# MSboard.net
KiCad netlist of a schematic drawn in EAGLE
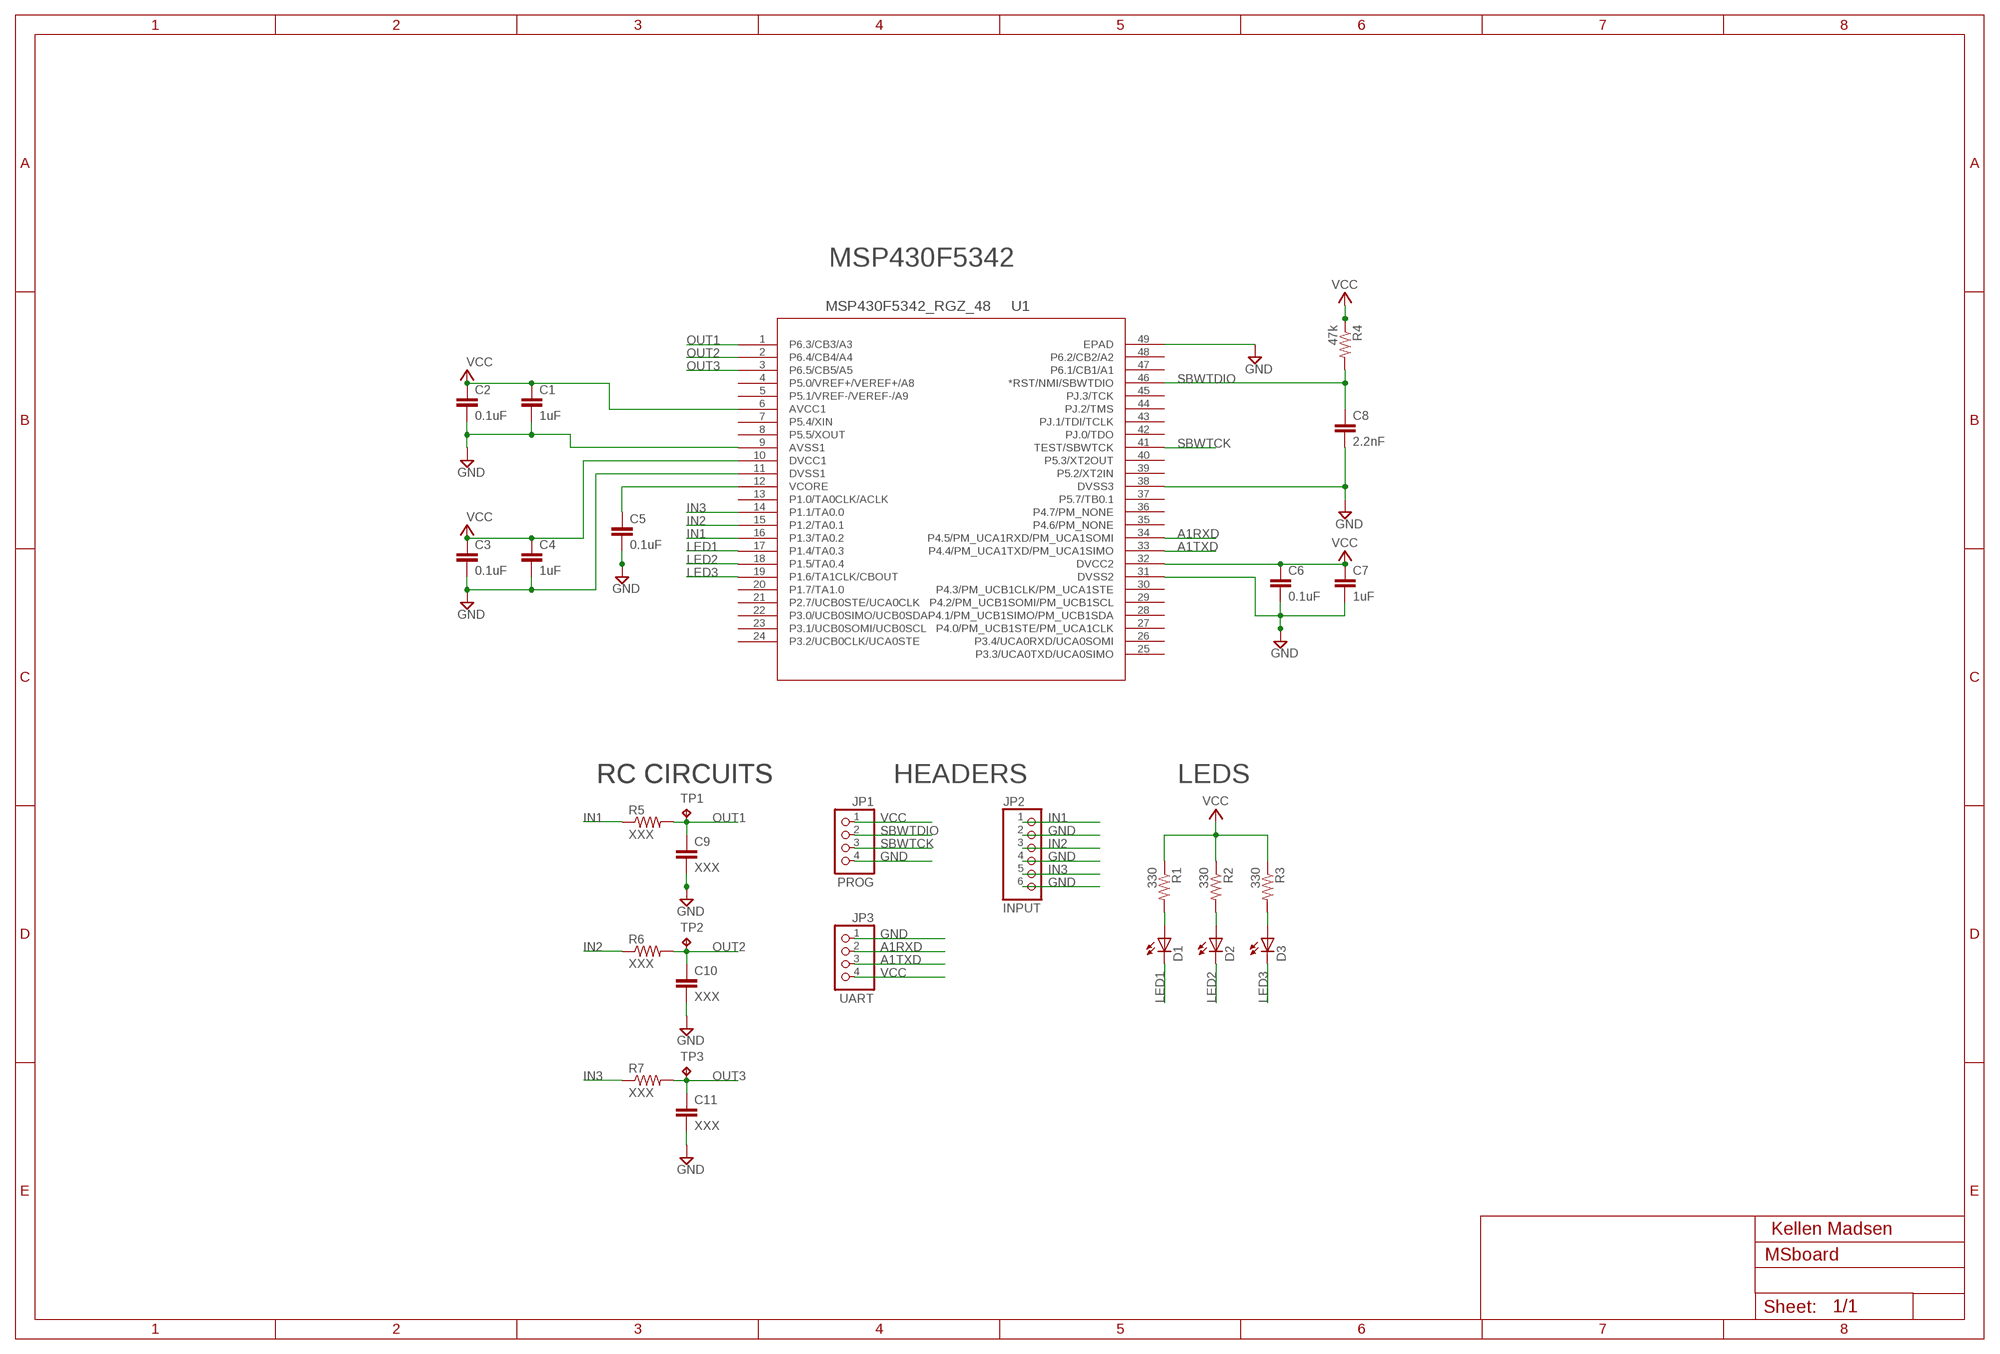
[diagram p0: schematic, sheet 1]

(export (version "E")
  (design (tool "Eeschema 10.0.6"))
  (components
    (comp (ref "C1")
      (value "1uF")
      (footprint "eagle-import:C0603")
      (libsource (lib "eagle-import") (part "C-EUC0603"))
    )
    (comp (ref "C2")
      (value "0.1uF")
      (footprint "eagle-import:C0603")
      (libsource (lib "eagle-import") (part "C-EUC0603"))
    )
    (comp (ref "C3")
      (value "0.1uF")
      (footprint "eagle-import:C0603")
      (libsource (lib "eagle-import") (part "C-EUC0603"))
    )
    (comp (ref "C4")
      (value "1uF")
      (footprint "eagle-import:C0603")
      (libsource (lib "eagle-import") (part "C-EUC0603"))
    )
    (comp (ref "C5")
      (value "0.1uF")
      (footprint "eagle-import:C0603")
      (libsource (lib "eagle-import") (part "C-EUC0603"))
    )
    (comp (ref "C6")
      (value "0.1uF")
      (footprint "eagle-import:C0603")
      (libsource (lib "eagle-import") (part "C-EUC0603"))
    )
    (comp (ref "C7")
      (value "1uF")
      (footprint "eagle-import:C0603")
      (libsource (lib "eagle-import") (part "C-EUC0603"))
    )
    (comp (ref "C8")
      (value "2.2nF")
      (footprint "eagle-import:C0603")
      (libsource (lib "eagle-import") (part "C-EUC0603"))
    )
    (comp (ref "C9")
      (value "XXX")
      (footprint "eagle-import:C0603")
      (libsource (lib "eagle-import") (part "C-EUC0603"))
    )
    (comp (ref "C10")
      (value "XXX")
      (footprint "eagle-import:C0603")
      (libsource (lib "eagle-import") (part "C-EUC0603"))
    )
    (comp (ref "C11")
      (value "XXX")
      (footprint "eagle-import:C0603")
      (libsource (lib "eagle-import") (part "C-EUC0603"))
    )
    (comp (ref "D1")
      (value "LEDCHIPLED_0603")
      (footprint "eagle-import:CHIPLED_0603")
      (libsource (lib "eagle-import") (part "LEDCHIPLED_0603"))
    )
    (comp (ref "D2")
      (value "LEDCHIPLED_0603")
      (footprint "eagle-import:CHIPLED_0603")
      (libsource (lib "eagle-import") (part "LEDCHIPLED_0603"))
    )
    (comp (ref "D3")
      (value "LEDCHIPLED_0603")
      (footprint "eagle-import:CHIPLED_0603")
      (libsource (lib "eagle-import") (part "LEDCHIPLED_0603"))
    )
    (comp (ref "JP1")
      (value "PROG")
      (footprint "eagle-import:1X04")
      (libsource (lib "eagle-import") (part "PINHD-1X4"))
    )
    (comp (ref "JP2")
      (value "INPUT")
      (footprint "eagle-import:1X06")
      (libsource (lib "eagle-import") (part "PINHD-1X6"))
    )
    (comp (ref "JP3")
      (value "UART")
      (footprint "eagle-import:1X04")
      (libsource (lib "eagle-import") (part "PINHD-1X4"))
    )
    (comp (ref "R1")
      (value "330")
      (footprint "eagle-import:R0603")
      (libsource (lib "eagle-import") (part "R-US_R0603"))
    )
    (comp (ref "R2")
      (value "330")
      (footprint "eagle-import:R0603")
      (libsource (lib "eagle-import") (part "R-US_R0603"))
    )
    (comp (ref "R3")
      (value "330")
      (footprint "eagle-import:R0603")
      (libsource (lib "eagle-import") (part "R-US_R0603"))
    )
    (comp (ref "R4")
      (value "47k")
      (footprint "eagle-import:R0603")
      (libsource (lib "eagle-import") (part "R-US_R0603"))
    )
    (comp (ref "R5")
      (value "XXX")
      (footprint "eagle-import:R0603")
      (libsource (lib "eagle-import") (part "R-US_R0603"))
    )
    (comp (ref "R6")
      (value "XXX")
      (footprint "eagle-import:R0603")
      (libsource (lib "eagle-import") (part "R-US_R0603"))
    )
    (comp (ref "R7")
      (value "XXX")
      (footprint "eagle-import:R0603")
      (libsource (lib "eagle-import") (part "R-US_R0603"))
    )
    (comp (ref "TP1")
      (value "TPPAD1-13Y")
      (footprint "eagle-import:P1-13Y")
      (libsource (lib "eagle-import") (part "TPPAD1-13Y"))
    )
    (comp (ref "TP2")
      (value "TPPAD1-13Y")
      (footprint "eagle-import:P1-13Y")
      (libsource (lib "eagle-import") (part "TPPAD1-13Y"))
    )
    (comp (ref "TP3")
      (value "TPPAD1-13Y")
      (footprint "eagle-import:P1-13Y")
      (libsource (lib "eagle-import") (part "TPPAD1-13Y"))
    )
    (comp (ref "U1")
      (value "MSP430F5342_RGZ_48")
      (footprint "eagle-import:RGZ48_5P15X5P15")
      (fields
        (field (name "GENERIC_PART_NUMBER") "MSP430F5342")
        (field (name "MANUFACTURER") "Texas Instruments")
        (field (name "MANUFACTURER_PART_NUMBER") "msp430f5342_rgz_48")
      )
      (libsource (lib "eagle-import") (part "MSP430F5342_RGZ_48"))
    )
  )
  (nets
    (net (code "1") (name "/A1RXD") (class "Default")
      (node (ref "JP3") (pin "2") (pinfunction "2_2") (pintype "passive"))
      (node (ref "U1") (pin "34") (pinfunction "P4.5/PM_UCA1RXD/PM_UCA1SOMI_34") (pintype "bidirectional"))
    )
    (net (code "2") (name "/A1TXD") (class "Default")
      (node (ref "JP3") (pin "3") (pinfunction "3_3") (pintype "passive"))
      (node (ref "U1") (pin "33") (pinfunction "P4.4/PM_UCA1TXD/PM_UCA1SIMO_33") (pintype "bidirectional"))
    )
    (net (code "3") (name "/IN1") (class "Default")
      (node (ref "JP2") (pin "1") (pinfunction "1_1") (pintype "passive"))
      (node (ref "R5") (pin "1") (pinfunction "1_1") (pintype "passive"))
      (node (ref "U1") (pin "16") (pinfunction "P1.3/TA0.2_16") (pintype "bidirectional"))
    )
    (net (code "4") (name "/IN2") (class "Default")
      (node (ref "JP2") (pin "3") (pinfunction "3_3") (pintype "passive"))
      (node (ref "R6") (pin "1") (pinfunction "1_1") (pintype "passive"))
      (node (ref "U1") (pin "15") (pinfunction "P1.2/TA0.1_15") (pintype "bidirectional"))
    )
    (net (code "5") (name "/IN3") (class "Default")
      (node (ref "JP2") (pin "5") (pinfunction "5_5") (pintype "passive"))
      (node (ref "R7") (pin "1") (pinfunction "1_1") (pintype "passive"))
      (node (ref "U1") (pin "14") (pinfunction "P1.1/TA0.0_14") (pintype "bidirectional"))
    )
    (net (code "6") (name "/LED1") (class "Default")
      (node (ref "D1") (pin "C") (pinfunction "C_C") (pintype "passive"))
      (node (ref "U1") (pin "17") (pinfunction "P1.4/TA0.3_17") (pintype "bidirectional"))
    )
    (net (code "7") (name "/LED2") (class "Default")
      (node (ref "D2") (pin "C") (pinfunction "C_C") (pintype "passive"))
      (node (ref "U1") (pin "18") (pinfunction "P1.5/TA0.4_18") (pintype "bidirectional"))
    )
    (net (code "8") (name "/LED3") (class "Default")
      (node (ref "D3") (pin "C") (pinfunction "C_C") (pintype "passive"))
      (node (ref "U1") (pin "19") (pinfunction "P1.6/TA1CLK/CBOUT_19") (pintype "bidirectional"))
    )
    (net (code "9") (name "/OUT1") (class "Default")
      (node (ref "C9") (pin "1") (pinfunction "1_1") (pintype "passive"))
      (node (ref "R5") (pin "2") (pinfunction "2_2") (pintype "passive"))
      (node (ref "TP1") (pin "TP") (pinfunction "TP_TP") (pintype "input"))
      (node (ref "U1") (pin "1") (pinfunction "P6.3/CB3/A3_1") (pintype "bidirectional"))
    )
    (net (code "10") (name "/OUT2") (class "Default")
      (node (ref "C10") (pin "1") (pinfunction "1_1") (pintype "passive"))
      (node (ref "R6") (pin "2") (pinfunction "2_2") (pintype "passive"))
      (node (ref "TP2") (pin "TP") (pinfunction "TP_TP") (pintype "input"))
      (node (ref "U1") (pin "2") (pinfunction "P6.4/CB4/A4_2") (pintype "bidirectional"))
    )
    (net (code "11") (name "/OUT3") (class "Default")
      (node (ref "C11") (pin "1") (pinfunction "1_1") (pintype "passive"))
      (node (ref "R7") (pin "2") (pinfunction "2_2") (pintype "passive"))
      (node (ref "TP3") (pin "TP") (pinfunction "TP_TP") (pintype "input"))
      (node (ref "U1") (pin "3") (pinfunction "P6.5/CB5/A5_3") (pintype "bidirectional"))
    )
    (net (code "12") (name "/SBWTCK") (class "Default")
      (node (ref "JP1") (pin "3") (pinfunction "3_3") (pintype "passive"))
      (node (ref "U1") (pin "41") (pinfunction "TEST/SBWTCK_41") (pintype "bidirectional"))
    )
    (net (code "13") (name "/SBWTDIO") (class "Default")
      (node (ref "C8") (pin "1") (pinfunction "1_1") (pintype "passive"))
      (node (ref "JP1") (pin "2") (pinfunction "2_2") (pintype "passive"))
      (node (ref "R4") (pin "2") (pinfunction "2_2") (pintype "passive"))
      (node (ref "U1") (pin "46") (pinfunction "*RST/NMI/SBWTDIO_46") (pintype "bidirectional"))
    )
    (net (code "14") (name "GND") (class "Default")
      (node (ref "C1") (pin "2") (pinfunction "2_2") (pintype "passive"))
      (node (ref "C10") (pin "2") (pinfunction "2_2") (pintype "passive"))
      (node (ref "C11") (pin "2") (pinfunction "2_2") (pintype "passive"))
      (node (ref "C2") (pin "2") (pinfunction "2_2") (pintype "passive"))
      (node (ref "C3") (pin "2") (pinfunction "2_2") (pintype "passive"))
      (node (ref "C4") (pin "2") (pinfunction "2_2") (pintype "passive"))
      (node (ref "C5") (pin "2") (pinfunction "2_2") (pintype "passive"))
      (node (ref "C6") (pin "2") (pinfunction "2_2") (pintype "passive"))
      (node (ref "C7") (pin "2") (pinfunction "2_2") (pintype "passive"))
      (node (ref "C8") (pin "2") (pinfunction "2_2") (pintype "passive"))
      (node (ref "C9") (pin "2") (pinfunction "2_2") (pintype "passive"))
      (node (ref "JP1") (pin "4") (pinfunction "4_4") (pintype "passive"))
      (node (ref "JP2") (pin "2") (pinfunction "2_2") (pintype "passive"))
      (node (ref "JP2") (pin "4") (pinfunction "4_4") (pintype "passive"))
      (node (ref "JP2") (pin "6") (pinfunction "6_6") (pintype "passive"))
      (node (ref "JP3") (pin "1") (pinfunction "1_1") (pintype "passive"))
      (node (ref "U1") (pin "11") (pinfunction "DVSS1_11") (pintype "power_in"))
      (node (ref "U1") (pin "31") (pinfunction "DVSS2_31") (pintype "power_in"))
      (node (ref "U1") (pin "38") (pinfunction "DVSS3_38") (pintype "power_in"))
      (node (ref "U1") (pin "49") (pinfunction "EPAD_49") (pintype "passive"))
      (node (ref "U1") (pin "9") (pinfunction "AVSS1_9") (pintype "power_in"))
    )
    (net (code "15") (name "Net-(D1-PadA)") (class "Default")
      (node (ref "D1") (pin "A") (pinfunction "A_A") (pintype "passive"))
      (node (ref "R1") (pin "2") (pinfunction "2_2") (pintype "passive"))
    )
    (net (code "16") (name "Net-(D2-PadA)") (class "Default")
      (node (ref "D2") (pin "A") (pinfunction "A_A") (pintype "passive"))
      (node (ref "R2") (pin "2") (pinfunction "2_2") (pintype "passive"))
    )
    (net (code "17") (name "Net-(D3-PadA)") (class "Default")
      (node (ref "D3") (pin "A") (pinfunction "A_A") (pintype "passive"))
      (node (ref "R3") (pin "2") (pinfunction "2_2") (pintype "passive"))
    )
    (net (code "18") (name "Net-(U1-VCORE)") (class "Default")
      (node (ref "C5") (pin "1") (pinfunction "1_1") (pintype "passive"))
      (node (ref "U1") (pin "12") (pinfunction "VCORE_12") (pintype "power_in"))
    )
    (net (code "19") (name "VCC") (class "Default")
      (node (ref "C1") (pin "1") (pinfunction "1_1") (pintype "passive"))
      (node (ref "C2") (pin "1") (pinfunction "1_1") (pintype "passive"))
      (node (ref "C3") (pin "1") (pinfunction "1_1") (pintype "passive"))
      (node (ref "C4") (pin "1") (pinfunction "1_1") (pintype "passive"))
      (node (ref "C6") (pin "1") (pinfunction "1_1") (pintype "passive"))
      (node (ref "C7") (pin "1") (pinfunction "1_1") (pintype "passive"))
      (node (ref "JP1") (pin "1") (pinfunction "1_1") (pintype "passive"))
      (node (ref "JP3") (pin "4") (pinfunction "4_4") (pintype "passive"))
      (node (ref "R1") (pin "1") (pinfunction "1_1") (pintype "passive"))
      (node (ref "R2") (pin "1") (pinfunction "1_1") (pintype "passive"))
      (node (ref "R3") (pin "1") (pinfunction "1_1") (pintype "passive"))
      (node (ref "R4") (pin "1") (pinfunction "1_1") (pintype "passive"))
      (node (ref "U1") (pin "10") (pinfunction "DVCC1_10") (pintype "power_in"))
      (node (ref "U1") (pin "32") (pinfunction "DVCC2_32") (pintype "power_in"))
      (node (ref "U1") (pin "6") (pinfunction "AVCC1_6") (pintype "power_in"))
    )
    (net (code "20") (name "unconnected-(U1-P1.0{slash}TA0CLK{slash}ACLK-Pad13)") (class "Default")
      (node (ref "U1") (pin "13") (pinfunction "P1.0/TA0CLK/ACLK_13") (pintype "bidirectional"))
    )
    (net (code "21") (name "unconnected-(U1-P1.7{slash}TA1.0-Pad20)") (class "Default")
      (node (ref "U1") (pin "20") (pinfunction "P1.7/TA1.0_20") (pintype "bidirectional"))
    )
    (net (code "22") (name "unconnected-(U1-P2.7{slash}UCB0STE{slash}UCA0CLK-Pad21)") (class "Default")
      (node (ref "U1") (pin "21") (pinfunction "P2.7/UCB0STE/UCA0CLK_21") (pintype "bidirectional"))
    )
    (net (code "23") (name "unconnected-(U1-P3.0{slash}UCB0SIMO{slash}UCB0SDA-Pad22)") (class "Default")
      (node (ref "U1") (pin "22") (pinfunction "P3.0/UCB0SIMO/UCB0SDA_22") (pintype "bidirectional"))
    )
    (net (code "24") (name "unconnected-(U1-P3.1{slash}UCB0SOMI{slash}UCB0SCL-Pad23)") (class "Default")
      (node (ref "U1") (pin "23") (pinfunction "P3.1/UCB0SOMI/UCB0SCL_23") (pintype "bidirectional"))
    )
    (net (code "25") (name "unconnected-(U1-P3.2{slash}UCB0CLK{slash}UCA0STE-Pad24)") (class "Default")
      (node (ref "U1") (pin "24") (pinfunction "P3.2/UCB0CLK/UCA0STE_24") (pintype "bidirectional"))
    )
    (net (code "26") (name "unconnected-(U1-P3.3{slash}UCA0TXD{slash}UCA0SIMO-Pad25)") (class "Default")
      (node (ref "U1") (pin "25") (pinfunction "P3.3/UCA0TXD/UCA0SIMO_25") (pintype "bidirectional"))
    )
    (net (code "27") (name "unconnected-(U1-P3.4{slash}UCA0RXD{slash}UCA0SOMI-Pad26)") (class "Default")
      (node (ref "U1") (pin "26") (pinfunction "P3.4/UCA0RXD/UCA0SOMI_26") (pintype "bidirectional"))
    )
    (net (code "28") (name "unconnected-(U1-P4.0{slash}PM_UCB1STE{slash}PM_UCA1CLK-Pad27)") (class "Default")
      (node (ref "U1") (pin "27") (pinfunction "P4.0/PM_UCB1STE/PM_UCA1CLK_27") (pintype "bidirectional"))
    )
    (net (code "29") (name "unconnected-(U1-P4.1{slash}PM_UCB1SIMO{slash}PM_UCB1SDA-Pad28)") (class "Default")
      (node (ref "U1") (pin "28") (pinfunction "P4.1/PM_UCB1SIMO/PM_UCB1SDA_28") (pintype "bidirectional"))
    )
    (net (code "30") (name "unconnected-(U1-P4.2{slash}PM_UCB1SOMI{slash}PM_UCB1SCL-Pad29)") (class "Default")
      (node (ref "U1") (pin "29") (pinfunction "P4.2/PM_UCB1SOMI/PM_UCB1SCL_29") (pintype "bidirectional"))
    )
    (net (code "31") (name "unconnected-(U1-P4.3{slash}PM_UCB1CLK{slash}PM_UCA1STE-Pad30)") (class "Default")
      (node (ref "U1") (pin "30") (pinfunction "P4.3/PM_UCB1CLK/PM_UCA1STE_30") (pintype "bidirectional"))
    )
    (net (code "32") (name "unconnected-(U1-P4.6{slash}PM_NONE-Pad35)") (class "Default")
      (node (ref "U1") (pin "35") (pinfunction "P4.6/PM_NONE_35") (pintype "bidirectional"))
    )
    (net (code "33") (name "unconnected-(U1-P4.7{slash}PM_NONE-Pad36)") (class "Default")
      (node (ref "U1") (pin "36") (pinfunction "P4.7/PM_NONE_36") (pintype "bidirectional"))
    )
    (net (code "34") (name "unconnected-(U1-P5.0{slash}VREF+{slash}VEREF+{slash}A8-Pad4)") (class "Default")
      (node (ref "U1") (pin "4") (pinfunction "P5.0/VREF+/VEREF+/A8_4") (pintype "bidirectional"))
    )
    (net (code "35") (name "unconnected-(U1-P5.1{slash}VREF-{slash}VEREF-{slash}A9-Pad5)") (class "Default")
      (node (ref "U1") (pin "5") (pinfunction "P5.1/VREF-/VEREF-/A9_5") (pintype "bidirectional"))
    )
    (net (code "36") (name "unconnected-(U1-P5.2{slash}XT2IN-Pad39)") (class "Default")
      (node (ref "U1") (pin "39") (pinfunction "P5.2/XT2IN_39") (pintype "bidirectional"))
    )
    (net (code "37") (name "unconnected-(U1-P5.3{slash}XT2OUT-Pad40)") (class "Default")
      (node (ref "U1") (pin "40") (pinfunction "P5.3/XT2OUT_40") (pintype "bidirectional"))
    )
    (net (code "38") (name "unconnected-(U1-P5.4{slash}XIN-Pad7)") (class "Default")
      (node (ref "U1") (pin "7") (pinfunction "P5.4/XIN_7") (pintype "bidirectional"))
    )
    (net (code "39") (name "unconnected-(U1-P5.5{slash}XOUT-Pad8)") (class "Default")
      (node (ref "U1") (pin "8") (pinfunction "P5.5/XOUT_8") (pintype "bidirectional"))
    )
    (net (code "40") (name "unconnected-(U1-P5.7{slash}TB0.1-Pad37)") (class "Default")
      (node (ref "U1") (pin "37") (pinfunction "P5.7/TB0.1_37") (pintype "bidirectional"))
    )
    (net (code "41") (name "unconnected-(U1-P6.1{slash}CB1{slash}A1-Pad47)") (class "Default")
      (node (ref "U1") (pin "47") (pinfunction "P6.1/CB1/A1_47") (pintype "bidirectional"))
    )
    (net (code "42") (name "unconnected-(U1-P6.2{slash}CB2{slash}A2-Pad48)") (class "Default")
      (node (ref "U1") (pin "48") (pinfunction "P6.2/CB2/A2_48") (pintype "bidirectional"))
    )
    (net (code "43") (name "unconnected-(U1-PJ.0{slash}TDO-Pad42)") (class "Default")
      (node (ref "U1") (pin "42") (pinfunction "PJ.0/TDO_42") (pintype "bidirectional"))
    )
    (net (code "44") (name "unconnected-(U1-PJ.1{slash}TDI{slash}TCLK-Pad43)") (class "Default")
      (node (ref "U1") (pin "43") (pinfunction "PJ.1/TDI/TCLK_43") (pintype "bidirectional"))
    )
    (net (code "45") (name "unconnected-(U1-PJ.2{slash}TMS-Pad44)") (class "Default")
      (node (ref "U1") (pin "44") (pinfunction "PJ.2/TMS_44") (pintype "bidirectional"))
    )
    (net (code "46") (name "unconnected-(U1-PJ.3{slash}TCK-Pad45)") (class "Default")
      (node (ref "U1") (pin "45") (pinfunction "PJ.3/TCK_45") (pintype "bidirectional"))
    )
  )
)
